# ECU_AutoRC_MOT_BEMF_r00.net
KiCad netlist of a schematic drawn in Altium Designer
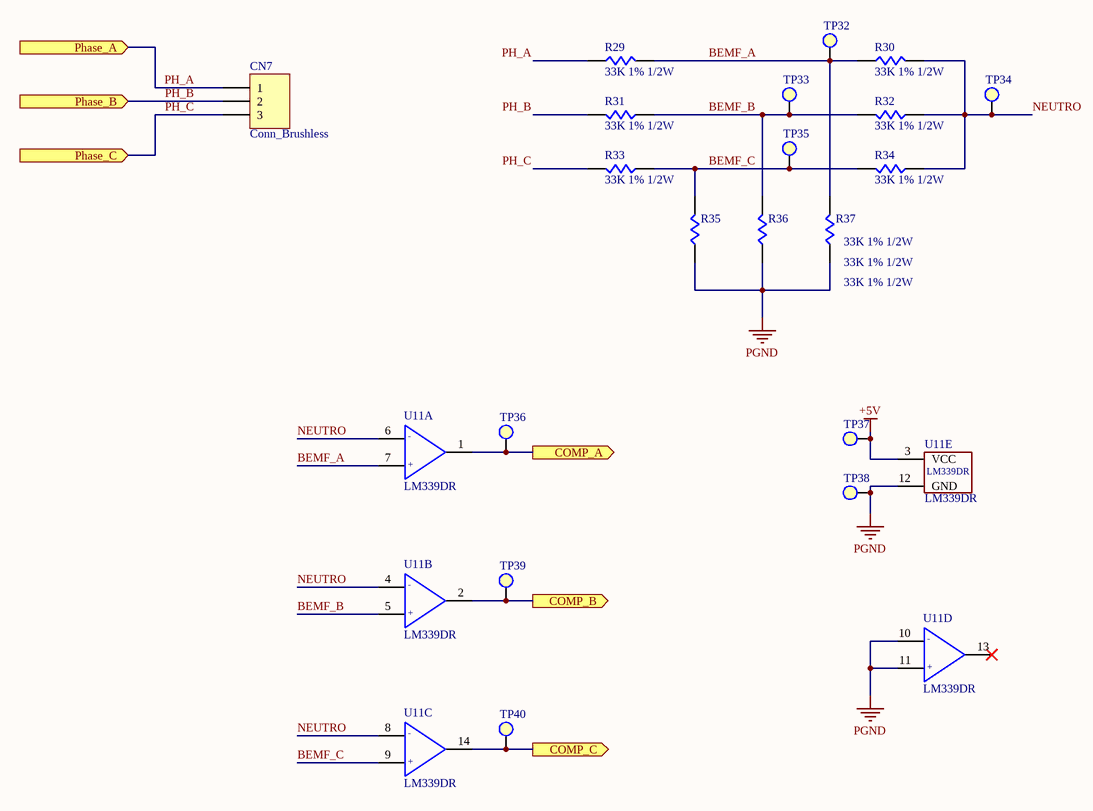
[diagram p0: ECU_AutoRC_MOT_BEMF_r00.SchDoc]

(export (version "E")
  (design (tool "Eeschema 10.0.6"))
  (components
    (comp (ref "CN7")
      (value "Conn_Brushless")
      (footprint "CONN_BRUSHLESS")
      (description "3 Pin Connector")
      (libsource (lib "ECU_AutoRC_r00") (part "CONN_03P"))
    )
    (comp (ref "R29")
      (value "33K 1% 1/2W")
      (footprint "R_0805")
      (description "Resistor")
      (libsource (lib "ECU_AutoRC_r00") (part "Resistor"))
    )
    (comp (ref "R30")
      (value "33K 1% 1/2W")
      (footprint "R_0805")
      (description "Resistor")
      (libsource (lib "ECU_AutoRC_r00") (part "Resistor"))
    )
    (comp (ref "R31")
      (value "33K 1% 1/2W")
      (footprint "R_0805")
      (description "Resistor")
      (libsource (lib "ECU_AutoRC_r00") (part "Resistor"))
    )
    (comp (ref "R32")
      (value "33K 1% 1/2W")
      (footprint "R_0805")
      (description "Resistor")
      (libsource (lib "ECU_AutoRC_r00") (part "Resistor"))
    )
    (comp (ref "R33")
      (value "33K 1% 1/2W")
      (footprint "R_0805")
      (description "Resistor")
      (libsource (lib "ECU_AutoRC_r00") (part "Resistor"))
    )
    (comp (ref "R34")
      (value "33K 1% 1/2W")
      (footprint "R_0805")
      (description "Resistor")
      (libsource (lib "ECU_AutoRC_r00") (part "Resistor"))
    )
    (comp (ref "R35")
      (value "33K 1% 1/2W")
      (footprint "R_0805")
      (description "Resistor")
      (libsource (lib "ECU_AutoRC_r00") (part "Resistor"))
    )
    (comp (ref "R36")
      (value "33K 1% 1/2W")
      (footprint "R_0805")
      (description "Resistor")
      (libsource (lib "ECU_AutoRC_r00") (part "Resistor"))
    )
    (comp (ref "R37")
      (value "33K 1% 1/2W")
      (footprint "R_0805")
      (description "Resistor")
      (libsource (lib "ECU_AutoRC_r00") (part "Resistor"))
    )
    (comp (ref "TP32")
      (value "Test Point")
      (footprint "TEST_POINT")
      (libsource (lib "ECU_AutoRC_r00") (part "TestPoint"))
    )
    (comp (ref "TP33")
      (value "Test Point")
      (footprint "TEST_POINT")
      (libsource (lib "ECU_AutoRC_r00") (part "TestPoint"))
    )
    (comp (ref "TP34")
      (value "Test Point")
      (footprint "TEST_POINT")
      (libsource (lib "ECU_AutoRC_r00") (part "TestPoint"))
    )
    (comp (ref "TP35")
      (value "Test Point")
      (footprint "TEST_POINT")
      (libsource (lib "ECU_AutoRC_r00") (part "TestPoint"))
    )
    (comp (ref "TP36")
      (value "Test Point")
      (footprint "TEST_POINT")
      (libsource (lib "ECU_AutoRC_r00") (part "TestPoint"))
    )
    (comp (ref "TP37")
      (value "Test Point")
      (footprint "TEST_POINT")
      (libsource (lib "ECU_AutoRC_r00") (part "TestPoint"))
    )
    (comp (ref "TP38")
      (value "Test Point")
      (footprint "TEST_POINT")
      (libsource (lib "ECU_AutoRC_r00") (part "TestPoint"))
    )
    (comp (ref "TP39")
      (value "Test Point")
      (footprint "TEST_POINT")
      (libsource (lib "ECU_AutoRC_r00") (part "TestPoint"))
    )
    (comp (ref "TP40")
      (value "Test Point")
      (footprint "TEST_POINT")
      (libsource (lib "ECU_AutoRC_r00") (part "TestPoint"))
    )
    (comp (ref "U11")
      (value "LM339DR")
      (footprint "SOIC14")
      (description "Comparator Standard Open-Collector 14-SOIC")
      (libsource (lib "ECU_AutoRC_r00") (part "LM339DR"))
    )
  )
  (nets
    (net (code "1") (name "+5V") (class "Default")
      (node (ref "TP37") (pin "1") (pintype "passive"))
      (node (ref "U11") (pin "3") (pinfunction "VCC_3") (pintype "power_in"))
    )
    (net (code "2") (name "/BEMF_A") (class "Default")
      (node (ref "R29") (pin "2") (pinfunction "2_2") (pintype "passive"))
      (node (ref "R30") (pin "1") (pinfunction "1_1") (pintype "passive"))
      (node (ref "R37") (pin "2") (pinfunction "2_2") (pintype "passive"))
      (node (ref "TP32") (pin "1") (pintype "passive"))
      (node (ref "U11") (pin "7") (pinfunction "IN1+_7") (pintype "passive"))
    )
    (net (code "3") (name "/BEMF_B") (class "Default")
      (node (ref "R31") (pin "1") (pinfunction "1_1") (pintype "passive"))
      (node (ref "R32") (pin "2") (pinfunction "2_2") (pintype "passive"))
      (node (ref "R36") (pin "2") (pinfunction "2_2") (pintype "passive"))
      (node (ref "TP33") (pin "1") (pintype "passive"))
      (node (ref "U11") (pin "5") (pinfunction "IN2+_5") (pintype "passive"))
    )
    (net (code "4") (name "/BEMF_C") (class "Default")
      (node (ref "R33") (pin "1") (pinfunction "1_1") (pintype "passive"))
      (node (ref "R34") (pin "2") (pinfunction "2_2") (pintype "passive"))
      (node (ref "R35") (pin "2") (pinfunction "2_2") (pintype "passive"))
      (node (ref "TP35") (pin "1") (pintype "passive"))
      (node (ref "U11") (pin "9") (pinfunction "IN3+_9") (pintype "passive"))
    )
    (net (code "5") (name "/COMP_A") (class "Default")
      (node (ref "TP36") (pin "1") (pintype "passive"))
      (node (ref "U11") (pin "1") (pinfunction "OUT1_1") (pintype "passive"))
    )
    (net (code "6") (name "/COMP_B") (class "Default")
      (node (ref "TP39") (pin "1") (pintype "passive"))
      (node (ref "U11") (pin "2") (pinfunction "OUT2_2") (pintype "passive"))
    )
    (net (code "7") (name "/COMP_C") (class "Default")
      (node (ref "TP40") (pin "1") (pintype "passive"))
      (node (ref "U11") (pin "14") (pinfunction "OUT3_14") (pintype "passive"))
    )
    (net (code "8") (name "/NEUTRO") (class "Default")
      (node (ref "R30") (pin "2") (pinfunction "2_2") (pintype "passive"))
      (node (ref "R32") (pin "1") (pinfunction "1_1") (pintype "passive"))
      (node (ref "R34") (pin "1") (pinfunction "1_1") (pintype "passive"))
      (node (ref "TP34") (pin "1") (pintype "passive"))
      (node (ref "U11") (pin "4") (pinfunction "IN2-_4") (pintype "passive"))
      (node (ref "U11") (pin "6") (pinfunction "IN1-_6") (pintype "passive"))
      (node (ref "U11") (pin "8") (pinfunction "IN3-_8") (pintype "passive"))
    )
    (net (code "9") (name "/PH_A") (class "Default")
      (node (ref "CN7") (pin "1") (pinfunction "1_1") (pintype "passive"))
      (node (ref "R29") (pin "1") (pinfunction "1_1") (pintype "passive"))
    )
    (net (code "10") (name "/PH_B") (class "Default")
      (node (ref "CN7") (pin "2") (pinfunction "2_2") (pintype "passive"))
      (node (ref "R31") (pin "2") (pinfunction "2_2") (pintype "passive"))
    )
    (net (code "11") (name "/PH_C") (class "Default")
      (node (ref "CN7") (pin "3") (pinfunction "3_3") (pintype "passive"))
      (node (ref "R33") (pin "2") (pinfunction "2_2") (pintype "passive"))
    )
    (net (code "12") (name "PGND") (class "Default")
      (node (ref "R35") (pin "1") (pinfunction "1_1") (pintype "passive"))
      (node (ref "R36") (pin "1") (pinfunction "1_1") (pintype "passive"))
      (node (ref "R37") (pin "1") (pinfunction "1_1") (pintype "passive"))
      (node (ref "TP38") (pin "1") (pintype "passive"))
      (node (ref "U11") (pin "10") (pinfunction "IN4-_10") (pintype "passive"))
      (node (ref "U11") (pin "11") (pinfunction "IN4+_11") (pintype "passive"))
      (node (ref "U11") (pin "12") (pinfunction "GND_12") (pintype "power_in"))
    )
    (net (code "13") (name "unconnected-(U11D-OUT4-Pad13)") (class "Default")
      (node (ref "U11") (pin "13") (pinfunction "OUT4_13") (pintype "passive+no_connect"))
    )
  )
)
